# PD.net
KiCad netlist of a schematic drawn in Altium Designer
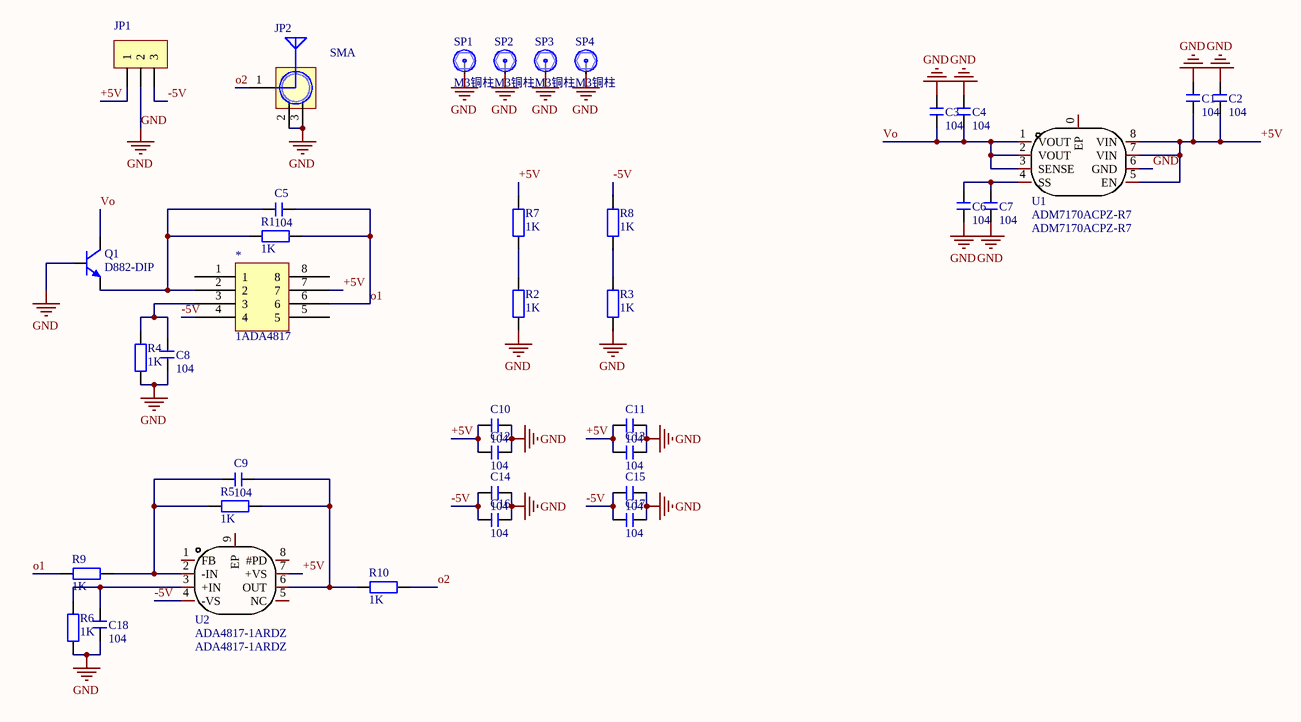
[diagram p0: PD.SchDoc]

(export (version "E")
  (design (tool "Eeschema 10.0.6"))
  (components
    (comp (ref "*") (value "1ADA4817") (footprint "SOP8_N") (libsource (lib "Schlib1") (part "Component_1")))
    (comp (ref "C1")
      (value "104")
      (footprint "C 0805_L")
      (description "无极性贴片电容")
      (libsource (lib "电容-电阻-电感-电位器") (part "C"))
    )
    (comp (ref "C2")
      (value "104")
      (footprint "C 0805_L")
      (description "无极性贴片电容")
      (libsource (lib "电容-电阻-电感-电位器") (part "C"))
    )
    (comp (ref "C3")
      (value "104")
      (footprint "C 0805_L")
      (description "无极性贴片电容")
      (libsource (lib "电容-电阻-电感-电位器") (part "C"))
    )
    (comp (ref "C4")
      (value "104")
      (footprint "C 0805_L")
      (description "无极性贴片电容")
      (libsource (lib "电容-电阻-电感-电位器") (part "C"))
    )
    (comp (ref "C5")
      (value "104")
      (footprint "C 0805_L")
      (description "无极性贴片电容")
      (libsource (lib "电容-电阻-电感-电位器") (part "C"))
    )
    (comp (ref "C6")
      (value "104")
      (footprint "C 0805_L")
      (description "无极性贴片电容")
      (libsource (lib "电容-电阻-电感-电位器") (part "C"))
    )
    (comp (ref "C7")
      (value "104")
      (footprint "C 0805_L")
      (description "无极性贴片电容")
      (libsource (lib "电容-电阻-电感-电位器") (part "C"))
    )
    (comp (ref "C8")
      (value "104")
      (footprint "C 0805_L")
      (description "无极性贴片电容")
      (libsource (lib "电容-电阻-电感-电位器") (part "C"))
    )
    (comp (ref "C9")
      (value "104")
      (footprint "C 0805_L")
      (description "无极性贴片电容")
      (libsource (lib "电容-电阻-电感-电位器") (part "C"))
    )
    (comp (ref "C10")
      (value "104")
      (footprint "C 0805_L")
      (description "无极性贴片电容")
      (libsource (lib "电容-电阻-电感-电位器") (part "C"))
    )
    (comp (ref "C11")
      (value "104")
      (footprint "C 0805_L")
      (description "无极性贴片电容")
      (libsource (lib "电容-电阻-电感-电位器") (part "C"))
    )
    (comp (ref "C12")
      (value "104")
      (footprint "C 0805_L")
      (description "无极性贴片电容")
      (libsource (lib "电容-电阻-电感-电位器") (part "C"))
    )
    (comp (ref "C13")
      (value "104")
      (footprint "C 0805_L")
      (description "无极性贴片电容")
      (libsource (lib "电容-电阻-电感-电位器") (part "C"))
    )
    (comp (ref "C14")
      (value "104")
      (footprint "C 0805_L")
      (description "无极性贴片电容")
      (libsource (lib "电容-电阻-电感-电位器") (part "C"))
    )
    (comp (ref "C15")
      (value "104")
      (footprint "C 0805_L")
      (description "无极性贴片电容")
      (libsource (lib "电容-电阻-电感-电位器") (part "C"))
    )
    (comp (ref "C16")
      (value "104")
      (footprint "C 0805_L")
      (description "无极性贴片电容")
      (libsource (lib "电容-电阻-电感-电位器") (part "C"))
    )
    (comp (ref "C17")
      (value "104")
      (footprint "C 0805_L")
      (description "无极性贴片电容")
      (libsource (lib "电容-电阻-电感-电位器") (part "C"))
    )
    (comp (ref "C18")
      (value "104")
      (footprint "C 0805_L")
      (description "无极性贴片电容")
      (libsource (lib "电容-电阻-电感-电位器") (part "C"))
    )
    (comp (ref "JP1")
      (value "HDR-1X3")
      (footprint "XH2.54-WI-3P")
      (description "3P接插件")
      (libsource (lib "XH2.54") (part "Header 3"))
    )
    (comp (ref "JP2")
      (value "SMA")
      (footprint "SMA-KE")
      (description "SMA-2.4G射频天线接口")
      (libsource (lib "天线") (part "SMA"))
    )
    (comp (ref "Q1")
      (value "D882-DIP")
      (footprint "TO92B")
      (description "音频功放-NPN型")
      (libsource (lib "三极管") (part "D882-DIP"))
    )
    (comp (ref "R1")
      (value "1K")
      (footprint "R 0805_L")
      (description "贴片电阻")
      (libsource (lib "电容-电阻-电感-电位器") (part "R"))
    )
    (comp (ref "R2")
      (value "1K")
      (footprint "R 0805_L")
      (description "贴片电阻")
      (libsource (lib "电容-电阻-电感-电位器") (part "R"))
    )
    (comp (ref "R3")
      (value "1K")
      (footprint "R 0805_L")
      (description "贴片电阻")
      (libsource (lib "电容-电阻-电感-电位器") (part "R"))
    )
    (comp (ref "R4")
      (value "1K")
      (footprint "R 0805_L")
      (description "贴片电阻")
      (libsource (lib "电容-电阻-电感-电位器") (part "R"))
    )
    (comp (ref "R5")
      (value "1K")
      (footprint "R 0805_L")
      (description "贴片电阻")
      (libsource (lib "电容-电阻-电感-电位器") (part "R"))
    )
    (comp (ref "R6")
      (value "1K")
      (footprint "R 0805_L")
      (description "贴片电阻")
      (libsource (lib "电容-电阻-电感-电位器") (part "R"))
    )
    (comp (ref "R7")
      (value "1K")
      (footprint "R 0805_L")
      (description "贴片电阻")
      (libsource (lib "电容-电阻-电感-电位器") (part "R"))
    )
    (comp (ref "R8")
      (value "1K")
      (footprint "R 0805_L")
      (description "贴片电阻")
      (libsource (lib "电容-电阻-电感-电位器") (part "R"))
    )
    (comp (ref "R9")
      (value "1K")
      (footprint "R 0805_L")
      (description "贴片电阻")
      (libsource (lib "电容-电阻-电感-电位器") (part "R"))
    )
    (comp (ref "R10")
      (value "1K")
      (footprint "R 0805_L")
      (description "贴片电阻")
      (libsource (lib "电容-电阻-电感-电位器") (part "R"))
    )
    (comp (ref "SP1")
      (value "M3铜柱")
      (footprint "M3x4_L")
      (description "铜柱")
      (libsource (lib "铜柱-测试点-电池座-蜂鸣器") (part "铜柱小焊盘"))
    )
    (comp (ref "SP2")
      (value "M3铜柱")
      (footprint "M3x4_L")
      (description "铜柱")
      (libsource (lib "铜柱-测试点-电池座-蜂鸣器") (part "铜柱小焊盘"))
    )
    (comp (ref "SP3")
      (value "M3铜柱")
      (footprint "M3x4_L")
      (description "铜柱")
      (libsource (lib "铜柱-测试点-电池座-蜂鸣器") (part "铜柱小焊盘"))
    )
    (comp (ref "SP4")
      (value "M3铜柱")
      (footprint "M3x4_L")
      (description "铜柱")
      (libsource (lib "铜柱-测试点-电池座-蜂鸣器") (part "铜柱小焊盘"))
    )
    (comp (ref "U1")
      (value "ADM7170ACPZ-R7")
      (footprint "LFCSP-8_L3.0-W3.0-P0.50-BL-EP")
      (fields (field (name "MANUFACTURER") "ADI(亚德诺)/LINEAR(凌特)") (field (name "NAME") "ADM7170ACPZ-R7"))
      (libsource (lib "adm7170") (part "ADM7170ACPZ-R7"))
    )
    (comp (ref "U2")
      (value "ADA4817-1ARDZ")
      (footprint "SOIC-8_L4.9-W3.9-P1.27-LS6.0-BL-EP2.3")
      (fields (field (name "MANUFACTURER") "ADI(亚德诺)/LINEAR") (field (name "NAME") "ADA4817-1ARDZ"))
      (libsource (lib "adm7170") (part "ADA4817-1ARDZ"))
    )
  )
  (nets
    (net (code "1") (name "/+5V") (class "Default")
      (node (ref "*") (pin "7") (pinfunction "7_7") (pintype "passive"))
      (node (ref "C1") (pin "1") (pinfunction "1_1") (pintype "passive"))
      (node (ref "C10") (pin "1") (pinfunction "1_1") (pintype "passive"))
      (node (ref "C11") (pin "1") (pinfunction "1_1") (pintype "passive"))
      (node (ref "C12") (pin "1") (pinfunction "1_1") (pintype "passive"))
      (node (ref "C13") (pin "1") (pinfunction "1_1") (pintype "passive"))
      (node (ref "C2") (pin "1") (pinfunction "1_1") (pintype "passive"))
      (node (ref "JP1") (pin "1") (pinfunction "1_1") (pintype "passive"))
      (node (ref "R7") (pin "2") (pinfunction "2_2") (pintype "passive"))
      (node (ref "U1") (pin "5") (pinfunction "EN_5") (pintype "passive"))
      (node (ref "U1") (pin "7") (pinfunction "VIN_7") (pintype "passive"))
      (node (ref "U1") (pin "8") (pinfunction "VIN_8") (pintype "passive"))
      (node (ref "U2") (pin "7") (pinfunction "+VS_7") (pintype "passive"))
    )
    (net (code "2") (name "/-5V") (class "Default")
      (node (ref "*") (pin "4") (pinfunction "4_4") (pintype "passive"))
      (node (ref "C14") (pin "1") (pinfunction "1_1") (pintype "passive"))
      (node (ref "C15") (pin "1") (pinfunction "1_1") (pintype "passive"))
      (node (ref "C16") (pin "1") (pinfunction "1_1") (pintype "passive"))
      (node (ref "C17") (pin "1") (pinfunction "1_1") (pintype "passive"))
      (node (ref "JP1") (pin "3") (pinfunction "3_3") (pintype "passive"))
      (node (ref "R8") (pin "2") (pinfunction "2_2") (pintype "passive"))
      (node (ref "U2") (pin "4") (pinfunction "-VS_4") (pintype "passive"))
    )
    (net (code "3") (name "/Vo") (class "Default")
      (node (ref "C3") (pin "1") (pinfunction "1_1") (pintype "passive"))
      (node (ref "C4") (pin "1") (pinfunction "1_1") (pintype "passive"))
      (node (ref "Q1") (pin "2") (pinfunction "C_2") (pintype "passive"))
      (node (ref "U1") (pin "1") (pinfunction "VOUT_1") (pintype "passive"))
      (node (ref "U1") (pin "2") (pinfunction "VOUT_2") (pintype "passive"))
      (node (ref "U1") (pin "3") (pinfunction "SENSE_3") (pintype "passive"))
    )
    (net (code "4") (name "/o1") (class "Default")
      (node (ref "*") (pin "6") (pinfunction "6_6") (pintype "passive"))
      (node (ref "C5") (pin "2") (pinfunction "2_2") (pintype "passive"))
      (node (ref "R1") (pin "2") (pinfunction "2_2") (pintype "passive"))
      (node (ref "R9") (pin "2") (pinfunction "2_2") (pintype "passive"))
    )
    (net (code "5") (name "/o2") (class "Default")
      (node (ref "JP2") (pin "1") (pinfunction "ANT_1") (pintype "passive"))
      (node (ref "R10") (pin "2") (pinfunction "2_2") (pintype "passive"))
    )
    (net (code "6") (name "GND") (class "Default")
      (node (ref "C1") (pin "2") (pinfunction "2_2") (pintype "passive"))
      (node (ref "C10") (pin "2") (pinfunction "2_2") (pintype "passive"))
      (node (ref "C11") (pin "2") (pinfunction "2_2") (pintype "passive"))
      (node (ref "C12") (pin "2") (pinfunction "2_2") (pintype "passive"))
      (node (ref "C13") (pin "2") (pinfunction "2_2") (pintype "passive"))
      (node (ref "C14") (pin "2") (pinfunction "2_2") (pintype "passive"))
      (node (ref "C15") (pin "2") (pinfunction "2_2") (pintype "passive"))
      (node (ref "C16") (pin "2") (pinfunction "2_2") (pintype "passive"))
      (node (ref "C17") (pin "2") (pinfunction "2_2") (pintype "passive"))
      (node (ref "C18") (pin "1") (pinfunction "1_1") (pintype "passive"))
      (node (ref "C2") (pin "2") (pinfunction "2_2") (pintype "passive"))
      (node (ref "C3") (pin "2") (pinfunction "2_2") (pintype "passive"))
      (node (ref "C4") (pin "2") (pinfunction "2_2") (pintype "passive"))
      (node (ref "C6") (pin "1") (pinfunction "1_1") (pintype "passive"))
      (node (ref "C7") (pin "1") (pinfunction "1_1") (pintype "passive"))
      (node (ref "C8") (pin "1") (pinfunction "1_1") (pintype "passive"))
      (node (ref "JP1") (pin "2") (pinfunction "2_2") (pintype "passive"))
      (node (ref "JP2") (pin "2") (pinfunction "GND_2") (pintype "passive"))
      (node (ref "JP2") (pin "3") (pinfunction "GND_3") (pintype "passive"))
      (node (ref "Q1") (pin "3") (pinfunction "B_3") (pintype "passive"))
      (node (ref "R2") (pin "1") (pinfunction "1_1") (pintype "passive"))
      (node (ref "R3") (pin "1") (pinfunction "1_1") (pintype "passive"))
      (node (ref "R4") (pin "1") (pinfunction "1_1") (pintype "passive"))
      (node (ref "R6") (pin "1") (pinfunction "1_1") (pintype "passive"))
      (node (ref "SP1") (pin "1") (pinfunction "1_1") (pintype "passive"))
      (node (ref "SP2") (pin "1") (pinfunction "1_1") (pintype "passive"))
      (node (ref "SP3") (pin "1") (pinfunction "1_1") (pintype "passive"))
      (node (ref "SP4") (pin "1") (pinfunction "1_1") (pintype "passive"))
      (node (ref "U1") (pin "6") (pinfunction "GND_6") (pintype "passive"))
    )
    (net (code "7") (name "Net-(*-Pad3)") (class "Default")
      (node (ref "*") (pin "3") (pinfunction "3_3") (pintype "passive"))
      (node (ref "C8") (pin "2") (pinfunction "2_2") (pintype "passive"))
      (node (ref "R4") (pin "2") (pinfunction "2_2") (pintype "passive"))
    )
    (net (code "8") (name "Net-(Q1-E)") (class "Default")
      (node (ref "*") (pin "2") (pinfunction "2_2") (pintype "passive"))
      (node (ref "C5") (pin "1") (pinfunction "1_1") (pintype "passive"))
      (node (ref "Q1") (pin "1") (pinfunction "E_1") (pintype "passive"))
      (node (ref "R1") (pin "1") (pinfunction "1_1") (pintype "passive"))
    )
    (net (code "9") (name "Net-(R2-Pad2)") (class "Default")
      (node (ref "R2") (pin "2") (pinfunction "2_2") (pintype "passive"))
      (node (ref "R7") (pin "1") (pinfunction "1_1") (pintype "passive"))
    )
    (net (code "10") (name "Net-(R3-Pad2)") (class "Default")
      (node (ref "R3") (pin "2") (pinfunction "2_2") (pintype "passive"))
      (node (ref "R8") (pin "1") (pinfunction "1_1") (pintype "passive"))
    )
    (net (code "11") (name "Net-(U1-SS)") (class "Default")
      (node (ref "C6") (pin "2") (pinfunction "2_2") (pintype "passive"))
      (node (ref "C7") (pin "2") (pinfunction "2_2") (pintype "passive"))
      (node (ref "U1") (pin "4") (pinfunction "SS_4") (pintype "passive"))
    )
    (net (code "12") (name "Net-(U2-+IN)") (class "Default")
      (node (ref "C18") (pin "2") (pinfunction "2_2") (pintype "passive"))
      (node (ref "R6") (pin "2") (pinfunction "2_2") (pintype "passive"))
      (node (ref "U2") (pin "3") (pinfunction "+IN_3") (pintype "passive"))
    )
    (net (code "13") (name "Net-(U2--IN)") (class "Default")
      (node (ref "C9") (pin "1") (pinfunction "1_1") (pintype "passive"))
      (node (ref "R5") (pin "2") (pinfunction "2_2") (pintype "passive"))
      (node (ref "R9") (pin "1") (pinfunction "1_1") (pintype "passive"))
      (node (ref "U2") (pin "2") (pinfunction "-IN_2") (pintype "passive"))
    )
    (net (code "14") (name "Net-(U2-OUT)") (class "Default")
      (node (ref "C9") (pin "2") (pinfunction "2_2") (pintype "passive"))
      (node (ref "R10") (pin "1") (pinfunction "1_1") (pintype "passive"))
      (node (ref "R5") (pin "1") (pinfunction "1_1") (pintype "passive"))
      (node (ref "U2") (pin "6") (pinfunction "OUT_6") (pintype "passive"))
    )
    (net (code "15") (name "unconnected-(*-Pad1)") (class "Default")
      (node (ref "*") (pin "1") (pinfunction "1_1") (pintype "passive"))
    )
    (net (code "16") (name "unconnected-(*-Pad5)") (class "Default")
      (node (ref "*") (pin "5") (pinfunction "5_5") (pintype "passive"))
    )
    (net (code "17") (name "unconnected-(*-Pad8)") (class "Default")
      (node (ref "*") (pin "8") (pinfunction "8_8") (pintype "passive"))
    )
    (net (code "18") (name "unconnected-(U1-EP-Pad0)") (class "Default")
      (node (ref "U1") (pin "0") (pinfunction "EP_0") (pintype "passive"))
    )
    (net (code "19") (name "unconnected-(U2-#PD-Pad8)") (class "Default")
      (node (ref "U2") (pin "8") (pinfunction "#PD_8") (pintype "passive"))
    )
    (net (code "20") (name "unconnected-(U2-EP-Pad9)") (class "Default")
      (node (ref "U2") (pin "9") (pinfunction "EP_9") (pintype "passive"))
    )
    (net (code "21") (name "unconnected-(U2-FB-Pad1)") (class "Default")
      (node (ref "U2") (pin "1") (pinfunction "FB_1") (pintype "passive"))
    )
    (net (code "22") (name "unconnected-(U2-NC-Pad5)") (class "Default")
      (node (ref "U2") (pin "5") (pinfunction "NC_5") (pintype "passive"))
    )
  )
)
